# User_Interface.net
KiCad netlist of a schematic drawn in Altium Designer
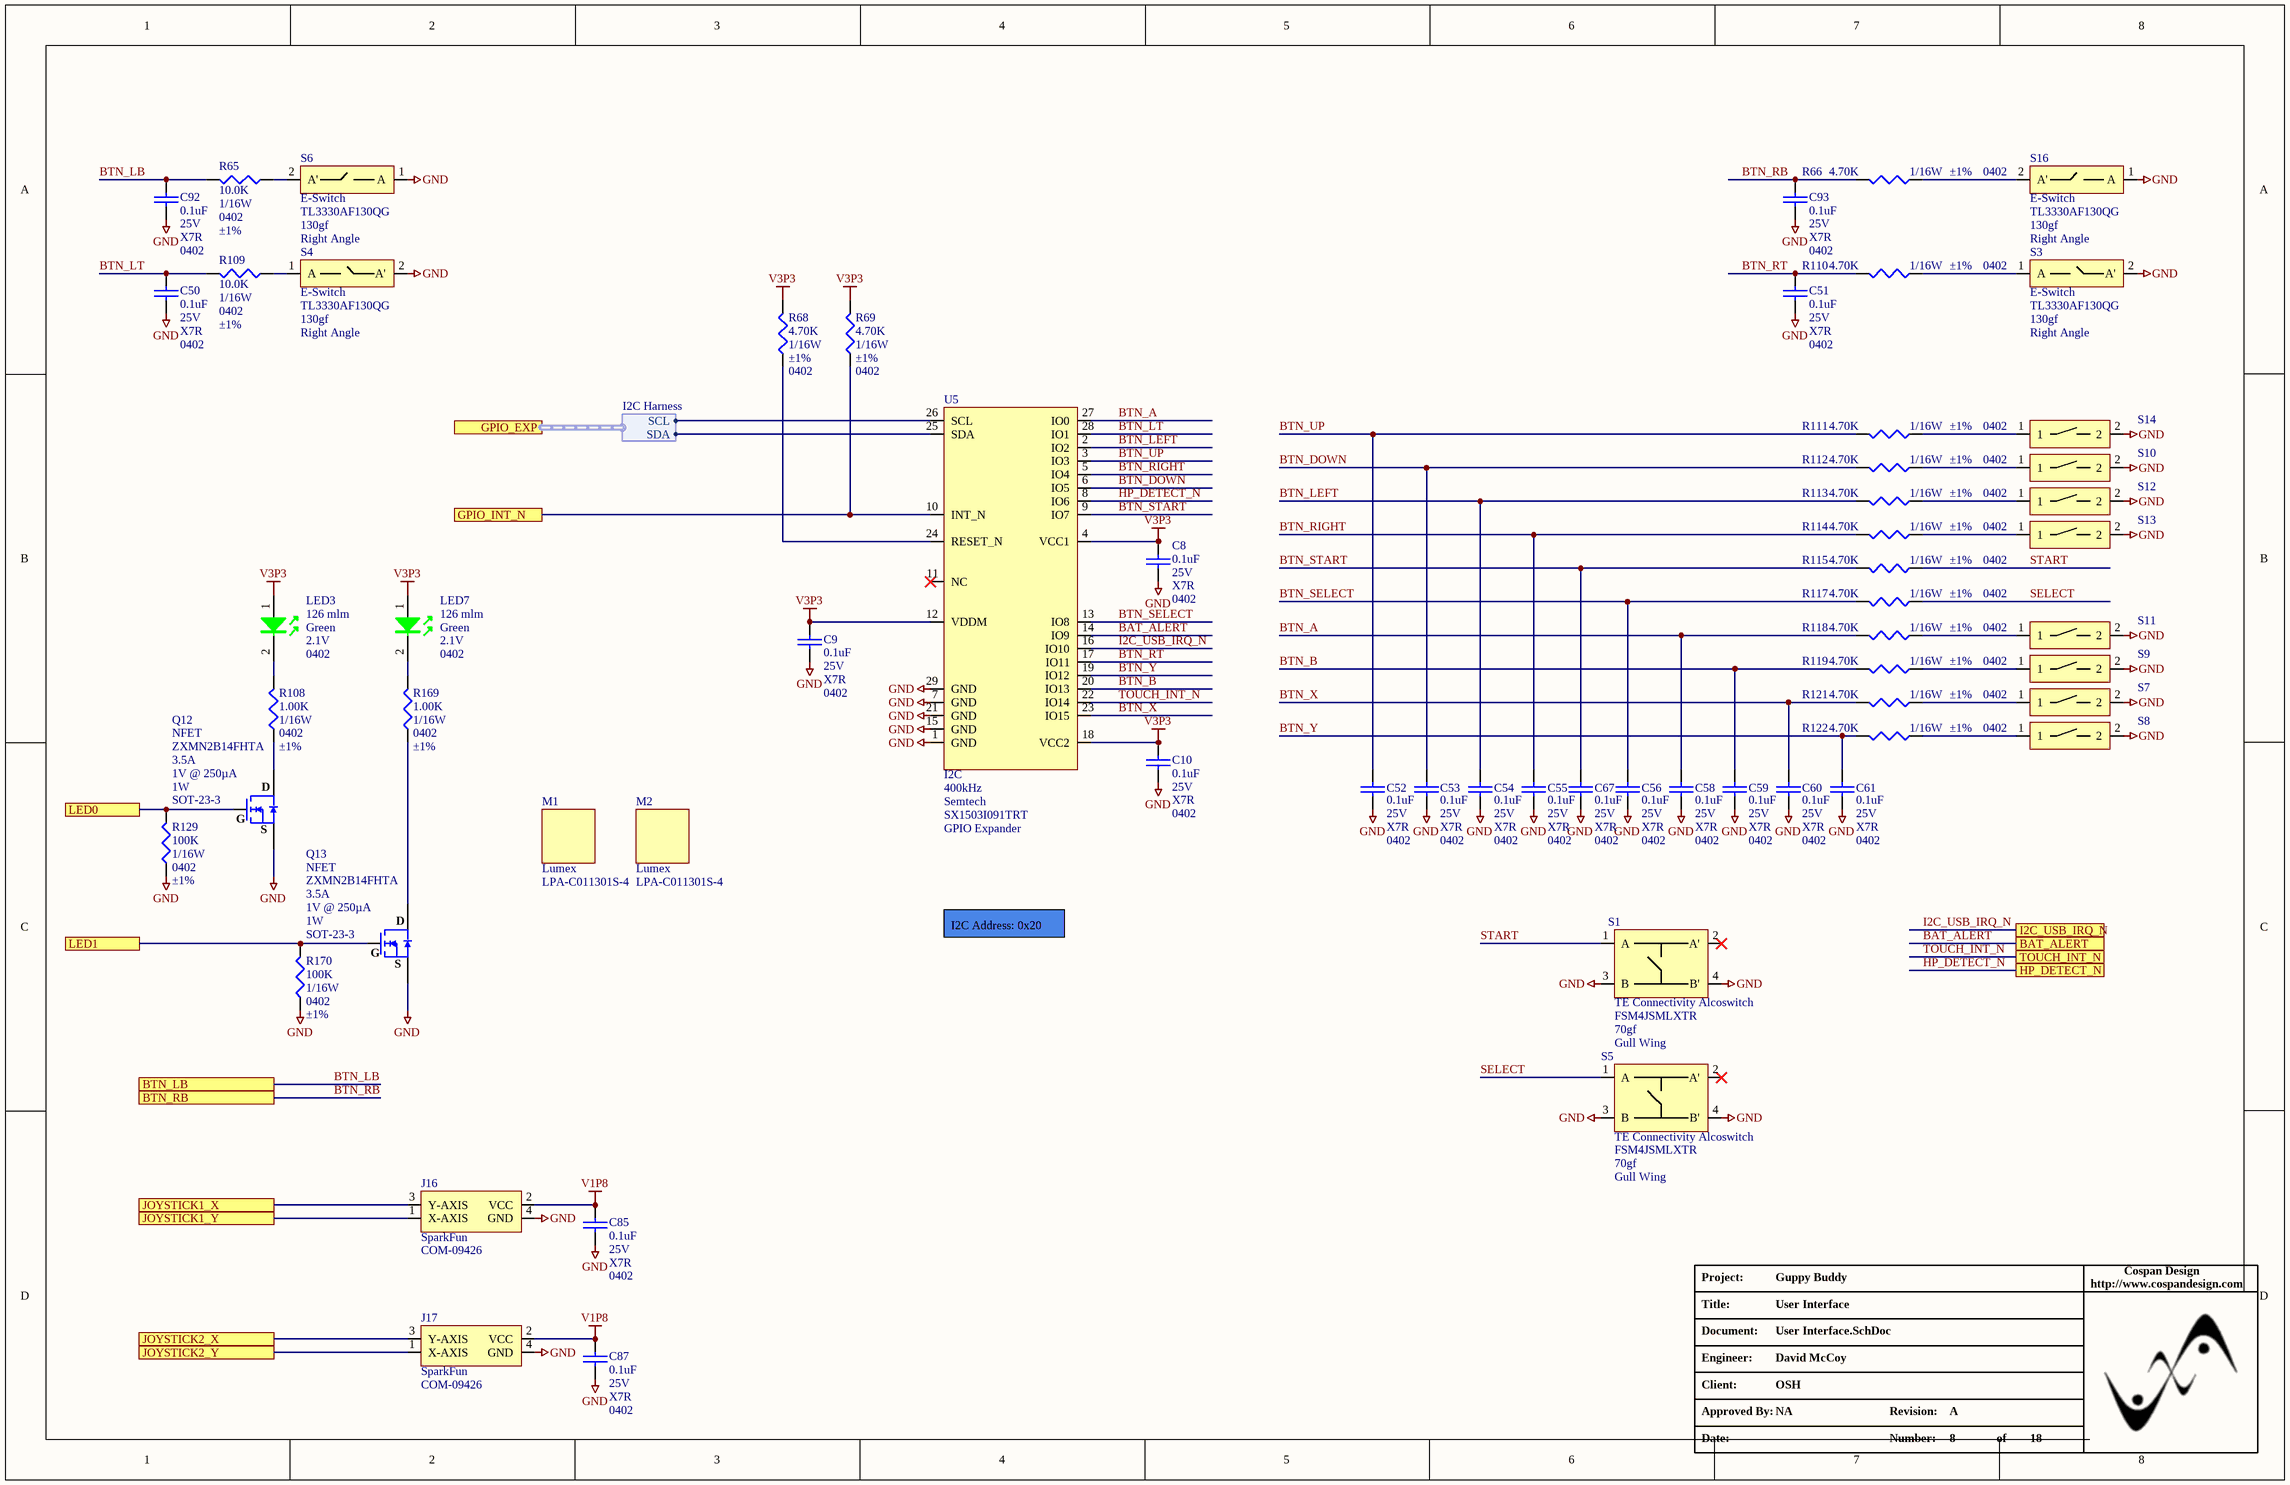
[diagram p0: User Interface.SchDoc]

(export (version "E")
  (design (tool "Eeschema 10.0.6"))
  (components
    (comp (ref "C8")
      (value "C_0402_0.1UF_25V")
      (footprint "C_0402")
      (description "CAP CER 0.1UF 25V X6S 0402")
      (fields
        (field (name "TOLERANCE") "10%")
        (field (name "CAPACITANCE") "0.1uF")
        (field (name "VOLTAGE - RATED") "25V")
        (field (name "TEMPERATURE COEFFICIENT") "X7R")
        (field (name "PACKAGE / CASE") "0402")
      )
      (libsource (lib "Cospan Design") (part "C_0402_0.1UF_25V"))
    )
    (comp (ref "C9")
      (value "C_0402_0.1UF_25V")
      (footprint "C_0402")
      (description "CAP CER 0.1UF 25V X6S 0402")
      (fields
        (field (name "TOLERANCE") "10%")
        (field (name "CAPACITANCE") "0.1uF")
        (field (name "VOLTAGE - RATED") "25V")
        (field (name "TEMPERATURE COEFFICIENT") "X7R")
        (field (name "PACKAGE / CASE") "0402")
      )
      (libsource (lib "Cospan Design") (part "C_0402_0.1UF_25V"))
    )
    (comp (ref "C10")
      (value "C_0402_0.1UF_25V")
      (footprint "C_0402")
      (description "CAP CER 0.1UF 25V X6S 0402")
      (fields
        (field (name "TOLERANCE") "10%")
        (field (name "CAPACITANCE") "0.1uF")
        (field (name "VOLTAGE - RATED") "25V")
        (field (name "TEMPERATURE COEFFICIENT") "X7R")
        (field (name "PACKAGE / CASE") "0402")
      )
      (libsource (lib "Cospan Design") (part "C_0402_0.1UF_25V"))
    )
    (comp (ref "C50")
      (value "C_0402_0.1UF_25V")
      (footprint "C_0402")
      (description "CAP CER 0.1UF 25V X6S 0402")
      (fields
        (field (name "TOLERANCE") "10%")
        (field (name "CAPACITANCE") "0.1uF")
        (field (name "VOLTAGE - RATED") "25V")
        (field (name "TEMPERATURE COEFFICIENT") "X7R")
        (field (name "PACKAGE / CASE") "0402")
      )
      (libsource (lib "Cospan Design") (part "C_0402_0.1UF_25V"))
    )
    (comp (ref "C51")
      (value "C_0402_0.1UF_25V")
      (footprint "C_0402")
      (description "CAP CER 0.1UF 25V X6S 0402")
      (fields
        (field (name "TOLERANCE") "10%")
        (field (name "CAPACITANCE") "0.1uF")
        (field (name "VOLTAGE - RATED") "25V")
        (field (name "TEMPERATURE COEFFICIENT") "X7R")
        (field (name "PACKAGE / CASE") "0402")
      )
      (libsource (lib "Cospan Design") (part "C_0402_0.1UF_25V"))
    )
    (comp (ref "C52")
      (value "C_0402_0.1UF_25V")
      (footprint "C_0402")
      (description "CAP CER 0.1UF 25V X6S 0402")
      (fields
        (field (name "TOLERANCE") "10%")
        (field (name "CAPACITANCE") "0.1uF")
        (field (name "VOLTAGE - RATED") "25V")
        (field (name "TEMPERATURE COEFFICIENT") "X7R")
        (field (name "PACKAGE / CASE") "0402")
      )
      (libsource (lib "Cospan Design") (part "C_0402_0.1UF_25V"))
    )
    (comp (ref "C53")
      (value "C_0402_0.1UF_25V")
      (footprint "C_0402")
      (description "CAP CER 0.1UF 25V X6S 0402")
      (fields
        (field (name "TOLERANCE") "10%")
        (field (name "CAPACITANCE") "0.1uF")
        (field (name "VOLTAGE - RATED") "25V")
        (field (name "TEMPERATURE COEFFICIENT") "X7R")
        (field (name "PACKAGE / CASE") "0402")
      )
      (libsource (lib "Cospan Design") (part "C_0402_0.1UF_25V"))
    )
    (comp (ref "C54")
      (value "C_0402_0.1UF_25V")
      (footprint "C_0402")
      (description "CAP CER 0.1UF 25V X6S 0402")
      (fields
        (field (name "TOLERANCE") "10%")
        (field (name "CAPACITANCE") "0.1uF")
        (field (name "VOLTAGE - RATED") "25V")
        (field (name "TEMPERATURE COEFFICIENT") "X7R")
        (field (name "PACKAGE / CASE") "0402")
      )
      (libsource (lib "Cospan Design") (part "C_0402_0.1UF_25V"))
    )
    (comp (ref "C55")
      (value "C_0402_0.1UF_25V")
      (footprint "C_0402")
      (description "CAP CER 0.1UF 25V X6S 0402")
      (fields
        (field (name "TOLERANCE") "10%")
        (field (name "CAPACITANCE") "0.1uF")
        (field (name "VOLTAGE - RATED") "25V")
        (field (name "TEMPERATURE COEFFICIENT") "X7R")
        (field (name "PACKAGE / CASE") "0402")
      )
      (libsource (lib "Cospan Design") (part "C_0402_0.1UF_25V"))
    )
    (comp (ref "C56")
      (value "C_0402_0.1UF_25V")
      (footprint "C_0402")
      (description "CAP CER 0.1UF 25V X6S 0402")
      (fields
        (field (name "TOLERANCE") "10%")
        (field (name "CAPACITANCE") "0.1uF")
        (field (name "VOLTAGE - RATED") "25V")
        (field (name "TEMPERATURE COEFFICIENT") "X7R")
        (field (name "PACKAGE / CASE") "0402")
      )
      (libsource (lib "Cospan Design") (part "C_0402_0.1UF_25V"))
    )
    (comp (ref "C58")
      (value "C_0402_0.1UF_25V")
      (footprint "C_0402")
      (description "CAP CER 0.1UF 25V X6S 0402")
      (fields
        (field (name "TOLERANCE") "10%")
        (field (name "CAPACITANCE") "0.1uF")
        (field (name "VOLTAGE - RATED") "25V")
        (field (name "TEMPERATURE COEFFICIENT") "X7R")
        (field (name "PACKAGE / CASE") "0402")
      )
      (libsource (lib "Cospan Design") (part "C_0402_0.1UF_25V"))
    )
    (comp (ref "C59")
      (value "C_0402_0.1UF_25V")
      (footprint "C_0402")
      (description "CAP CER 0.1UF 25V X6S 0402")
      (fields
        (field (name "TOLERANCE") "10%")
        (field (name "CAPACITANCE") "0.1uF")
        (field (name "VOLTAGE - RATED") "25V")
        (field (name "TEMPERATURE COEFFICIENT") "X7R")
        (field (name "PACKAGE / CASE") "0402")
      )
      (libsource (lib "Cospan Design") (part "C_0402_0.1UF_25V"))
    )
    (comp (ref "C60")
      (value "C_0402_0.1UF_25V")
      (footprint "C_0402")
      (description "CAP CER 0.1UF 25V X6S 0402")
      (fields
        (field (name "TOLERANCE") "10%")
        (field (name "CAPACITANCE") "0.1uF")
        (field (name "VOLTAGE - RATED") "25V")
        (field (name "TEMPERATURE COEFFICIENT") "X7R")
        (field (name "PACKAGE / CASE") "0402")
      )
      (libsource (lib "Cospan Design") (part "C_0402_0.1UF_25V"))
    )
    (comp (ref "C61")
      (value "C_0402_0.1UF_25V")
      (footprint "C_0402")
      (description "CAP CER 0.1UF 25V X6S 0402")
      (fields
        (field (name "TOLERANCE") "10%")
        (field (name "CAPACITANCE") "0.1uF")
        (field (name "VOLTAGE - RATED") "25V")
        (field (name "TEMPERATURE COEFFICIENT") "X7R")
        (field (name "PACKAGE / CASE") "0402")
      )
      (libsource (lib "Cospan Design") (part "C_0402_0.1UF_25V"))
    )
    (comp (ref "C67")
      (value "C_0402_0.1UF_25V")
      (footprint "C_0402")
      (description "CAP CER 0.1UF 25V X6S 0402")
      (fields
        (field (name "TOLERANCE") "10%")
        (field (name "CAPACITANCE") "0.1uF")
        (field (name "VOLTAGE - RATED") "25V")
        (field (name "TEMPERATURE COEFFICIENT") "X7R")
        (field (name "PACKAGE / CASE") "0402")
      )
      (libsource (lib "Cospan Design") (part "C_0402_0.1UF_25V"))
    )
    (comp (ref "C85")
      (value "C_0402_0.1UF_25V")
      (footprint "C_0402")
      (description "CAP CER 0.1UF 25V X6S 0402")
      (fields
        (field (name "TOLERANCE") "10%")
        (field (name "CAPACITANCE") "0.1uF")
        (field (name "VOLTAGE - RATED") "25V")
        (field (name "TEMPERATURE COEFFICIENT") "X7R")
        (field (name "PACKAGE / CASE") "0402")
      )
      (libsource (lib "Cospan Design") (part "C_0402_0.1UF_25V"))
    )
    (comp (ref "C87")
      (value "C_0402_0.1UF_25V")
      (footprint "C_0402")
      (description "CAP CER 0.1UF 25V X6S 0402")
      (fields
        (field (name "TOLERANCE") "10%")
        (field (name "CAPACITANCE") "0.1uF")
        (field (name "VOLTAGE - RATED") "25V")
        (field (name "TEMPERATURE COEFFICIENT") "X7R")
        (field (name "PACKAGE / CASE") "0402")
      )
      (libsource (lib "Cospan Design") (part "C_0402_0.1UF_25V"))
    )
    (comp (ref "C92")
      (value "C_0402_0.1UF_25V")
      (footprint "C_0402")
      (description "CAP CER 0.1UF 25V X6S 0402")
      (fields
        (field (name "TOLERANCE") "10%")
        (field (name "CAPACITANCE") "0.1uF")
        (field (name "VOLTAGE - RATED") "25V")
        (field (name "TEMPERATURE COEFFICIENT") "X7R")
        (field (name "PACKAGE / CASE") "0402")
      )
      (libsource (lib "Cospan Design") (part "C_0402_0.1UF_25V"))
    )
    (comp (ref "C93")
      (value "C_0402_0.1UF_25V")
      (footprint "C_0402")
      (description "CAP CER 0.1UF 25V X6S 0402")
      (fields
        (field (name "TOLERANCE") "10%")
        (field (name "CAPACITANCE") "0.1uF")
        (field (name "VOLTAGE - RATED") "25V")
        (field (name "TEMPERATURE COEFFICIENT") "X7R")
        (field (name "PACKAGE / CASE") "0402")
      )
      (libsource (lib "Cospan Design") (part "C_0402_0.1UF_25V"))
    )
    (comp (ref "J16")
      (value "J_PSP1000")
      (footprint "JOYSTICK_PSP1000")
      (description "THUMB SLIDE JOYSTICK")
      (fields
        (field (name "MANUFACTURER 1") "SparkFun")
        (field (name "MANUFACTURER PART NUMBER 1") "COM-09426")
      )
      (libsource (lib "Cospan Design") (part "J_PSP1000"))
    )
    (comp (ref "J17")
      (value "J_PSP1000")
      (footprint "JOYSTICK_PSP1000")
      (description "THUMB SLIDE JOYSTICK")
      (fields
        (field (name "MANUFACTURER 1") "SparkFun")
        (field (name "MANUFACTURER PART NUMBER 1") "COM-09426")
      )
      (libsource (lib "Cospan Design") (part "J_PSP1000"))
    )
    (comp (ref "LED3")
      (value "LED_GRN_0402")
      (footprint "DIOM1005X07L_GREEN")
      (description "LED 1X0.5MM 570NM GN WTR CLR SMD")
      (fields
        (field (name "MANUFACTURER") "Kingbright Corp")
        (field (name "MANUFACTURER PART NUMBER") "APHHS1005CGCK")
        (field (name "LUMINOUS FLUX @ CURRENT - TEST") "126 mlm")
        (field (name "COLOR") "Green")
        (field (name "VOLTAGE - FORWARD (VF) TYP") "2.1V")
        (field (name "PACKAGE / CASE") "0402")
      )
      (libsource (lib "Main Library") (part "LED_GRN_0402"))
    )
    (comp (ref "LED7")
      (value "LED_GRN_0402")
      (footprint "DIOM1005X07L_GREEN")
      (description "LED 1X0.5MM 570NM GN WTR CLR SMD")
      (fields
        (field (name "MANUFACTURER") "Kingbright Corp")
        (field (name "MANUFACTURER PART NUMBER") "APHHS1005CGCK")
        (field (name "LUMINOUS FLUX @ CURRENT - TEST") "126 mlm")
        (field (name "COLOR") "Green")
        (field (name "VOLTAGE - FORWARD (VF) TYP") "2.1V")
        (field (name "PACKAGE / CASE") "0402")
      )
      (libsource (lib "Main Library") (part "LED_GRN_0402"))
    )
    (comp (ref "M1")
      (value "M_LIGHT_PIPE")
      (footprint "SINGLE_LIGHT_PIPE")
      (description "LIGHT PIPE 4MM SINGLE VERT SMD")
      (fields
        (field (name "MANUFACTURER 1") "Lumex")
        (field (name "MANUFACTURER PART NUMBER 1") "LPA-C011301S-4")
      )
      (libsource (lib "Cospan Design") (part "M_LIGHT_PIPE"))
    )
    (comp (ref "M2")
      (value "M_LIGHT_PIPE")
      (footprint "SINGLE_LIGHT_PIPE")
      (description "LIGHT PIPE 4MM SINGLE VERT SMD")
      (fields
        (field (name "MANUFACTURER 1") "Lumex")
        (field (name "MANUFACTURER PART NUMBER 1") "LPA-C011301S-4")
      )
      (libsource (lib "Cospan Design") (part "M_LIGHT_PIPE"))
    )
    (comp (ref "Q12")
      (value "NFET")
      (footprint "SOT-23A")
      (description "MOSFET N-CH 20V 3.5A SOT23-3")
      (fields
        (field (name "MANUFACTURER") "Diodes Incorporated")
        (field (name "MANUFACTURER PART NUMBER") "ZXMN2B14FHTA")
        (field (name "CURRENT - CONTINUOUS DRAIN (ID) @ 25° C") "3.5A")
        (field (name "VGS(TH) (MAX) @ ID") "1V @ 250µA")
        (field (name "POWER - MAX") "1W")
        (field (name "PACKAGE / CASE") "SOT-23-3")
      )
      (libsource (lib "Main LibraryX") (part "Q_NFET_3.50A_SOT23"))
    )
    (comp (ref "Q13")
      (value "NFET")
      (footprint "SOT-23A")
      (description "MOSFET N-CH 20V 3.5A SOT23-3")
      (fields
        (field (name "MANUFACTURER") "Diodes Incorporated")
        (field (name "MANUFACTURER PART NUMBER") "ZXMN2B14FHTA")
        (field (name "CURRENT - CONTINUOUS DRAIN (ID) @ 25° C") "3.5A")
        (field (name "VGS(TH) (MAX) @ ID") "1V @ 250µA")
        (field (name "POWER - MAX") "1W")
        (field (name "PACKAGE / CASE") "SOT-23-3")
      )
      (libsource (lib "Main LibraryX") (part "Q_NFET_3.50A_SOT23"))
    )
    (comp (ref "R65")
      (value "R_0402_10.0K")
      (footprint "R_0402")
      (description "RES 10.0K OHM 1/16W 1% 0402 SMD")
      (fields
        (field (name "MANUFACTURER") "Stackpole Electronics Inc")
        (field (name "MANUFACTURER PART NUMBER") "RMCF0402FT10K0")
        (field (name "RESISTANCE IN OHMS") "10.0K")
        (field (name "POWER (WATTS)") "1/16W")
        (field (name "CASE") "0402")
        (field (name "TOLERANCE") "±1%")
      )
      (libsource (lib "Cospan Design") (part "R_0402_10.0K"))
    )
    (comp (ref "R66")
      (value "4.7k Ohms")
      (footprint "R_0402")
      (description "RES 4.70K OHM 1/16W 1% 0402 SMD")
      (fields
        (field (name "MANUFACTURER") "Yageo")
        (field (name "MANUFACTURER PART NUMBER") "RC0402FR-074K7L")
        (field (name "RESISTANCE IN OHMS") "4.70K")
        (field (name "POWER (WATTS)") "1/16W")
        (field (name "TOLERANCE") "±1%")
        (field (name "CASE") "0402")
      )
      (libsource (lib "Main Library") (part "R_0402_4.70K"))
    )
    (comp (ref "R68")
      (value "4.7k Ohms")
      (footprint "R_0402")
      (description "RES 4.70K OHM 1/16W 1% 0402 SMD")
      (fields
        (field (name "MANUFACTURER") "Yageo")
        (field (name "MANUFACTURER PART NUMBER") "RC0402FR-074K7L")
        (field (name "RESISTANCE IN OHMS") "4.70K")
        (field (name "POWER (WATTS)") "1/16W")
        (field (name "TOLERANCE") "±1%")
        (field (name "CASE") "0402")
      )
      (libsource (lib "Main Library") (part "R_0402_4.70K"))
    )
    (comp (ref "R69")
      (value "4.7k Ohms")
      (footprint "R_0402")
      (description "RES 4.70K OHM 1/16W 1% 0402 SMD")
      (fields
        (field (name "MANUFACTURER") "Yageo")
        (field (name "MANUFACTURER PART NUMBER") "RC0402FR-074K7L")
        (field (name "RESISTANCE IN OHMS") "4.70K")
        (field (name "POWER (WATTS)") "1/16W")
        (field (name "TOLERANCE") "±1%")
        (field (name "CASE") "0402")
      )
      (libsource (lib "Main Library") (part "R_0402_4.70K"))
    )
    (comp (ref "R108")
      (value "1.0k Ohms")
      (footprint "R_0402")
      (description "RES 1.00K OHM 1/16W 1% 0402 SMD")
      (fields
        (field (name "MANUFACTURER") "Yageo")
        (field (name "MANUFACTURER PART NUMBER") "RC0402FR-071KL")
        (field (name "RESISTANCE IN OHMS") "1.00K")
        (field (name "POWER (WATTS)") "1/16W")
        (field (name "CASE") "0402")
        (field (name "TOLERANCE") "±1%")
      )
      (libsource (lib "Main Library") (part "R_0402_1.0K"))
    )
    (comp (ref "R109")
      (value "R_0402_10.0K")
      (footprint "R_0402")
      (description "RES 10.0K OHM 1/16W 1% 0402 SMD")
      (fields
        (field (name "MANUFACTURER") "Stackpole Electronics Inc")
        (field (name "MANUFACTURER PART NUMBER") "RMCF0402FT10K0")
        (field (name "RESISTANCE IN OHMS") "10.0K")
        (field (name "POWER (WATTS)") "1/16W")
        (field (name "CASE") "0402")
        (field (name "TOLERANCE") "±1%")
      )
      (libsource (lib "Cospan Design") (part "R_0402_10.0K"))
    )
    (comp (ref "R110")
      (value "4.7k Ohms")
      (footprint "R_0402")
      (description "RES 4.70K OHM 1/16W 1% 0402 SMD")
      (fields
        (field (name "MANUFACTURER") "Yageo")
        (field (name "MANUFACTURER PART NUMBER") "RC0402FR-074K7L")
        (field (name "RESISTANCE IN OHMS") "4.70K")
        (field (name "POWER (WATTS)") "1/16W")
        (field (name "TOLERANCE") "±1%")
        (field (name "CASE") "0402")
      )
      (libsource (lib "Main Library") (part "R_0402_4.70K"))
    )
    (comp (ref "R111")
      (value "4.7k Ohms")
      (footprint "R_0402")
      (description "RES 4.70K OHM 1/16W 1% 0402 SMD")
      (fields
        (field (name "MANUFACTURER") "Yageo")
        (field (name "MANUFACTURER PART NUMBER") "RC0402FR-074K7L")
        (field (name "RESISTANCE IN OHMS") "4.70K")
        (field (name "POWER (WATTS)") "1/16W")
        (field (name "TOLERANCE") "±1%")
        (field (name "CASE") "0402")
      )
      (libsource (lib "Main Library") (part "R_0402_4.70K"))
    )
    (comp (ref "R112")
      (value "4.7k Ohms")
      (footprint "R_0402")
      (description "RES 4.70K OHM 1/16W 1% 0402 SMD")
      (fields
        (field (name "MANUFACTURER") "Yageo")
        (field (name "MANUFACTURER PART NUMBER") "RC0402FR-074K7L")
        (field (name "RESISTANCE IN OHMS") "4.70K")
        (field (name "POWER (WATTS)") "1/16W")
        (field (name "TOLERANCE") "±1%")
        (field (name "CASE") "0402")
      )
      (libsource (lib "Main Library") (part "R_0402_4.70K"))
    )
    (comp (ref "R113")
      (value "4.7k Ohms")
      (footprint "R_0402")
      (description "RES 4.70K OHM 1/16W 1% 0402 SMD")
      (fields
        (field (name "MANUFACTURER") "Yageo")
        (field (name "MANUFACTURER PART NUMBER") "RC0402FR-074K7L")
        (field (name "RESISTANCE IN OHMS") "4.70K")
        (field (name "POWER (WATTS)") "1/16W")
        (field (name "TOLERANCE") "±1%")
        (field (name "CASE") "0402")
      )
      (libsource (lib "Main Library") (part "R_0402_4.70K"))
    )
    (comp (ref "R114")
      (value "4.7k Ohms")
      (footprint "R_0402")
      (description "RES 4.70K OHM 1/16W 1% 0402 SMD")
      (fields
        (field (name "MANUFACTURER") "Yageo")
        (field (name "MANUFACTURER PART NUMBER") "RC0402FR-074K7L")
        (field (name "RESISTANCE IN OHMS") "4.70K")
        (field (name "POWER (WATTS)") "1/16W")
        (field (name "TOLERANCE") "±1%")
        (field (name "CASE") "0402")
      )
      (libsource (lib "Main Library") (part "R_0402_4.70K"))
    )
    (comp (ref "R115")
      (value "4.7k Ohms")
      (footprint "R_0402")
      (description "RES 4.70K OHM 1/16W 1% 0402 SMD")
      (fields
        (field (name "MANUFACTURER") "Yageo")
        (field (name "MANUFACTURER PART NUMBER") "RC0402FR-074K7L")
        (field (name "RESISTANCE IN OHMS") "4.70K")
        (field (name "POWER (WATTS)") "1/16W")
        (field (name "TOLERANCE") "±1%")
        (field (name "CASE") "0402")
      )
      (libsource (lib "Main Library") (part "R_0402_4.70K"))
    )
    (comp (ref "R117")
      (value "4.7k Ohms")
      (footprint "R_0402")
      (description "RES 4.70K OHM 1/16W 1% 0402 SMD")
      (fields
        (field (name "MANUFACTURER") "Yageo")
        (field (name "MANUFACTURER PART NUMBER") "RC0402FR-074K7L")
        (field (name "RESISTANCE IN OHMS") "4.70K")
        (field (name "POWER (WATTS)") "1/16W")
        (field (name "TOLERANCE") "±1%")
        (field (name "CASE") "0402")
      )
      (libsource (lib "Main Library") (part "R_0402_4.70K"))
    )
    (comp (ref "R118")
      (value "4.7k Ohms")
      (footprint "R_0402")
      (description "RES 4.70K OHM 1/16W 1% 0402 SMD")
      (fields
        (field (name "MANUFACTURER") "Yageo")
        (field (name "MANUFACTURER PART NUMBER") "RC0402FR-074K7L")
        (field (name "RESISTANCE IN OHMS") "4.70K")
        (field (name "POWER (WATTS)") "1/16W")
        (field (name "TOLERANCE") "±1%")
        (field (name "CASE") "0402")
      )
      (libsource (lib "Main Library") (part "R_0402_4.70K"))
    )
    (comp (ref "R119")
      (value "4.7k Ohms")
      (footprint "R_0402")
      (description "RES 4.70K OHM 1/16W 1% 0402 SMD")
      (fields
        (field (name "MANUFACTURER") "Yageo")
        (field (name "MANUFACTURER PART NUMBER") "RC0402FR-074K7L")
        (field (name "RESISTANCE IN OHMS") "4.70K")
        (field (name "POWER (WATTS)") "1/16W")
        (field (name "TOLERANCE") "±1%")
        (field (name "CASE") "0402")
      )
      (libsource (lib "Main Library") (part "R_0402_4.70K"))
    )
    (comp (ref "R121")
      (value "4.7k Ohms")
      (footprint "R_0402")
      (description "RES 4.70K OHM 1/16W 1% 0402 SMD")
      (fields
        (field (name "MANUFACTURER") "Yageo")
        (field (name "MANUFACTURER PART NUMBER") "RC0402FR-074K7L")
        (field (name "RESISTANCE IN OHMS") "4.70K")
        (field (name "POWER (WATTS)") "1/16W")
        (field (name "TOLERANCE") "±1%")
        (field (name "CASE") "0402")
      )
      (libsource (lib "Main Library") (part "R_0402_4.70K"))
    )
    (comp (ref "R122")
      (value "4.7k Ohms")
      (footprint "R_0402")
      (description "RES 4.70K OHM 1/16W 1% 0402 SMD")
      (fields
        (field (name "MANUFACTURER") "Yageo")
        (field (name "MANUFACTURER PART NUMBER") "RC0402FR-074K7L")
        (field (name "RESISTANCE IN OHMS") "4.70K")
        (field (name "POWER (WATTS)") "1/16W")
        (field (name "TOLERANCE") "±1%")
        (field (name "CASE") "0402")
      )
      (libsource (lib "Main Library") (part "R_0402_4.70K"))
    )
    (comp (ref "R129")
      (value "R_0402_100.0K")
      (footprint "R_0402")
      (description "RES 100K OHM 1/16W 1% 0402 SMD")
      (fields
        (field (name "MANUFACTURER") "Stackpole Electronics Inc")
        (field (name "MANUFACTURER PART NUMBER") "RMCF0402FT100K")
        (field (name "RESISTANCE IN OHMS") "100K")
        (field (name "POWER (WATTS)") "1/16W")
        (field (name "CASE") "0402")
        (field (name "TOLERANCE") "±1%")
      )
      (libsource (lib "Main Library") (part "R_0402_100.0K"))
    )
    (comp (ref "R169")
      (value "1.0k Ohms")
      (footprint "R_0402")
      (description "RES 1.00K OHM 1/16W 1% 0402 SMD")
      (fields
        (field (name "MANUFACTURER") "Yageo")
        (field (name "MANUFACTURER PART NUMBER") "RC0402FR-071KL")
        (field (name "RESISTANCE IN OHMS") "1.00K")
        (field (name "POWER (WATTS)") "1/16W")
        (field (name "CASE") "0402")
        (field (name "TOLERANCE") "±1%")
      )
      (libsource (lib "Main Library") (part "R_0402_1.0K"))
    )
    (comp (ref "R170")
      (value "R_0402_100.0K")
      (footprint "R_0402")
      (description "RES 100K OHM 1/16W 1% 0402 SMD")
      (fields
        (field (name "MANUFACTURER") "Stackpole Electronics Inc")
        (field (name "MANUFACTURER PART NUMBER") "RMCF0402FT100K")
        (field (name "RESISTANCE IN OHMS") "100K")
        (field (name "POWER (WATTS)") "1/16W")
        (field (name "CASE") "0402")
        (field (name "TOLERANCE") "±1%")
      )
      (libsource (lib "Main Library") (part "R_0402_100.0K"))
    )
    (comp (ref "S1")
      (value "S_TACTILE_1571563_2_BUTTON")
      (footprint "TACTILE_1571563_2")
      (description "SWITCH TACTILE SPST-NO 0.05A 24V")
      (fields
        (field (name "MANUFACTURER") "TE Connectivity Alcoswitch")
        (field (name "MANUFACTURER PART NUMBER") "FSM4JSMLXTR")
        (field (name "OPERATING FORCE") "70gf")
        (field (name "TERMINATION") "Gull Wing")
      )
      (libsource (lib "Cospan Design") (part "S_TACTILE_1571563_2_BUTTON"))
    )
    (comp (ref "S3")
      (value "S_TACTILE_ RA_TL3330AF130QG_BUTTON")
      (footprint "TL3330AF130QG")
      (description "SWITCH TACTILE SPST-NO 0.05A 12V")
      (fields
        (field (name "MANUFACTURER") "E-Switch")
        (field (name "MANUFACTURER PART NUMBER") "TL3330AF130QG")
        (field (name "OPERATING FORCE") "130gf")
        (field (name "ORIENTATION") "Right Angle")
      )
      (libsource (lib "Cospan Design") (part "S_TACTILE_ RA_TL3330AF130QG_BUTTON"))
    )
    (comp (ref "S4")
      (value "S_TACTILE_ RA_TL3330AF130QG_BUTTON")
      (footprint "TL3330AF130QG")
      (description "SWITCH TACTILE SPST-NO 0.05A 12V")
      (fields
        (field (name "MANUFACTURER") "E-Switch")
        (field (name "MANUFACTURER PART NUMBER") "TL3330AF130QG")
        (field (name "OPERATING FORCE") "130gf")
        (field (name "ORIENTATION") "Right Angle")
      )
      (libsource (lib "Cospan Design") (part "S_TACTILE_ RA_TL3330AF130QG_BUTTON"))
    )
    (comp (ref "S5")
      (value "S_TACTILE_1571563_2_BUTTON")
      (footprint "TACTILE_1571563_2")
      (description "SWITCH TACTILE SPST-NO 0.05A 24V")
      (fields
        (field (name "MANUFACTURER") "TE Connectivity Alcoswitch")
        (field (name "MANUFACTURER PART NUMBER") "FSM4JSMLXTR")
        (field (name "OPERATING FORCE") "70gf")
        (field (name "TERMINATION") "Gull Wing")
      )
      (libsource (lib "Cospan Design") (part "S_TACTILE_1571563_2_BUTTON"))
    )
    (comp (ref "S6")
      (value "S_TACTILE_ RA_TL3330AF130QG_BUTTON")
      (footprint "TL3330AF130QG")
      (description "SWITCH TACTILE SPST-NO 0.05A 12V")
      (fields
        (field (name "MANUFACTURER") "E-Switch")
        (field (name "MANUFACTURER PART NUMBER") "TL3330AF130QG")
        (field (name "OPERATING FORCE") "130gf")
        (field (name "ORIENTATION") "Right Angle")
      )
      (libsource (lib "") (part "S_TACTILE_ RA_TL3330AF130QG_BUTTON_1"))
    )
    (comp (ref "S7")
      (value "S_GB_BTN")
      (footprint "GB_BUTTON")
      (libsource (lib "Cospan Design") (part "S_GB_BTN"))
    )
    (comp (ref "S8")
      (value "S_GB_BTN")
      (footprint "GB_BUTTON")
      (libsource (lib "Cospan Design") (part "S_GB_BTN"))
    )
    (comp (ref "S9")
      (value "S_GB_BTN")
      (footprint "GB_BUTTON")
      (libsource (lib "Cospan Design") (part "S_GB_BTN"))
    )
    (comp (ref "S10")
      (value "S_GB_BTN")
      (footprint "GB_BUTTON")
      (libsource (lib "Cospan Design") (part "S_GB_BTN"))
    )
    (comp (ref "S11")
      (value "S_GB_BTN")
      (footprint "GB_BUTTON")
      (libsource (lib "Cospan Design") (part "S_GB_BTN"))
    )
    (comp (ref "S12")
      (value "S_GB_BTN")
      (footprint "GB_BUTTON")
      (libsource (lib "Cospan Design") (part "S_GB_BTN"))
    )
    (comp (ref "S13")
      (value "S_GB_BTN")
      (footprint "GB_BUTTON")
      (libsource (lib "Cospan Design") (part "S_GB_BTN"))
    )
    (comp (ref "S14")
      (value "S_GB_BTN")
      (footprint "GB_BUTTON")
      (libsource (lib "Cospan Design") (part "S_GB_BTN"))
    )
    (comp (ref "S16")
      (value "S_TACTILE_ RA_TL3330AF130QG_BUTTON")
      (footprint "TL3330AF130QG")
      (description "SWITCH TACTILE SPST-NO 0.05A 12V")
      (fields
        (field (name "MANUFACTURER") "E-Switch")
        (field (name "MANUFACTURER PART NUMBER") "TL3330AF130QG")
        (field (name "OPERATING FORCE") "130gf")
        (field (name "ORIENTATION") "Right Angle")
      )
      (libsource (lib "") (part "S_TACTILE_ RA_TL3330AF130QG_BUTTON_1"))
    )
    (comp (ref "U5")
      (value "U_SX1503I091TRT")
      (footprint "QFN40P400X400X60_HS-29N")
      (description "IC GPIO EXPANDER I2C 16CH 28-QFN")
      (fields
        (field (name "INTERFACE") "I2C")
        (field (name "FREQUENCY") "400kHz")
        (field (name "MANUFACTURER 1") "Semtech")
        (field (name "MANUFACTURER PART NUMBER 1") "SX1503I091TRT")
        (field (name "SHORT DESC") "GPIO Expander")
      )
      (libsource (lib "Cospan Design") (part "U_SX1503I091TRT"))
    )
  )
  (nets
    (net (code "3") (name "/BAT_ALERT") (class "Default")
      (node (ref "U5") (pin "14") (pinfunction "IO9_14") (pintype "passive"))
    )
    (net (code "4") (name "/BTN_A") (class "Default")
      (node (ref "C58") (pin "2") (pinfunction "2_2") (pintype "passive"))
      (node (ref "R118") (pin "1") (pinfunction "1_1") (pintype "passive"))
      (node (ref "U5") (pin "27") (pinfunction "IO0_27") (pintype "passive"))
    )
    (net (code "5") (name "/BTN_B") (class "Default")
      (node (ref "C59") (pin "2") (pinfunction "2_2") (pintype "passive"))
      (node (ref "R119") (pin "1") (pinfunction "1_1") (pintype "passive"))
      (node (ref "U5") (pin "20") (pinfunction "IO13_20") (pintype "passive"))
    )
    (net (code "6") (name "/BTN_DOWN") (class "Default")
      (node (ref "C53") (pin "2") (pinfunction "2_2") (pintype "passive"))
      (node (ref "R112") (pin "1") (pinfunction "1_1") (pintype "passive"))
      (node (ref "U5") (pin "6") (pinfunction "IO5_6") (pintype "passive"))
    )
    (net (code "7") (name "/BTN_LB") (class "Default")
      (node (ref "C92") (pin "2") (pinfunction "2_2") (pintype "passive"))
      (node (ref "R65") (pin "1") (pinfunction "1_1") (pintype "passive"))
    )
    (net (code "8") (name "/BTN_LEFT") (class "Default")
      (node (ref "C54") (pin "2") (pinfunction "2_2") (pintype "passive"))
      (node (ref "R113") (pin "1") (pinfunction "1_1") (pintype "passive"))
      (node (ref "U5") (pin "2") (pinfunction "IO2_2") (pintype "passive"))
    )
    (net (code "9") (name "/BTN_LT") (class "Default")
      (node (ref "C50") (pin "2") (pinfunction "2_2") (pintype "passive"))
      (node (ref "R109") (pin "1") (pinfunction "1_1") (pintype "passive"))
      (node (ref "U5") (pin "28") (pinfunction "IO1_28") (pintype "passive"))
    )
    (net (code "10") (name "/BTN_RB") (class "Default")
      (node (ref "C93") (pin "2") (pinfunction "2_2") (pintype "passive"))
      (node (ref "R66") (pin "1") (pinfunction "1_1") (pintype "passive"))
    )
    (net (code "11") (name "/BTN_RIGHT") (class "Default")
      (node (ref "C55") (pin "2") (pinfunction "2_2") (pintype "passive"))
      (node (ref "R114") (pin "1") (pinfunction "1_1") (pintype "passive"))
      (node (ref "U5") (pin "5") (pinfunction "IO4_5") (pintype "passive"))
    )
    (net (code "12") (name "/BTN_RT") (class "Default")
      (node (ref "C51") (pin "2") (pinfunction "2_2") (pintype "passive"))
      (node (ref "R110") (pin "1") (pinfunction "1_1") (pintype "passive"))
      (node (ref "U5") (pin "17") (pinfunction "IO11_17") (pintype "passive"))
    )
    (net (code "13") (name "/BTN_SELECT") (class "Default")
      (node (ref "C56") (pin "2") (pinfunction "2_2") (pintype "passive"))
      (node (ref "R117") (pin "1") (pinfunction "1_1") (pintype "passive"))
      (node (ref "U5") (pin "13") (pinfunction "IO8_13") (pintype "passive"))
    )
    (net (code "14") (name "/BTN_START") (class "Default")
      (node (ref "C67") (pin "2") (pinfunction "2_2") (pintype "passive"))
      (node (ref "R115") (pin "1") (pinfunction "1_1") (pintype "passive"))
      (node (ref "U5") (pin "9") (pinfunction "IO7_9") (pintype "passive"))
    )
    (net (code "15") (name "/BTN_UP") (class "Default")
      (node (ref "C52") (pin "2") (pinfunction "2_2") (pintype "passive"))
      (node (ref "R111") (pin "1") (pinfunction "1_1") (pintype "passive"))
      (node (ref "U5") (pin "3") (pinfunction "IO3_3") (pintype "passive"))
    )
    (net (code "16") (name "/BTN_X") (class "Default")
      (node (ref "C60") (pin "2") (pinfunction "2_2") (pintype "passive"))
      (node (ref "R121") (pin "1") (pinfunction "1_1") (pintype "passive"))
      (node (ref "U5") (pin "23") (pinfunction "IO15_23") (pintype "passive"))
    )
    (net (code "17") (name "/BTN_Y") (class "Default")
      (node (ref "C61") (pin "2") (pinfunction "2_2") (pintype "passive"))
      (node (ref "R122") (pin "1") (pinfunction "1_1") (pintype "passive"))
      (node (ref "U5") (pin "19") (pinfunction "IO12_19") (pintype "passive"))
    )
    (net (code "18") (name "/GPIO_INT_N") (class "Default")
      (node (ref "R69") (pin "2") (pinfunction "2_2") (pintype "passive"))
      (node (ref "U5") (pin "10") (pinfunction "INT_N_10") (pintype "passive"))
    )
    (net (code "19") (name "/HP_DETECT_N") (class "Default")
      (node (ref "U5") (pin "8") (pinfunction "IO6_8") (pintype "passive"))
    )
    (net (code "20") (name "/I2C_USB_IRQ_N") (class "Default")
      (node (ref "U5") (pin "16") (pinfunction "IO10_16") (pintype "passive"))
    )
    (net (code "21") (name "/JOYSTICK1_X") (class "Default")
      (node (ref "J16") (pin "3") (pinfunction "Y-AXIS_3") (pintype "passive"))
    )
    (net (code "22") (name "/JOYSTICK1_Y") (class "Default")
      (node (ref "J16") (pin "1") (pinfunction "X-AXIS_1") (pintype "passive"))
    )
    (net (code "23") (name "/JOYSTICK2_X") (class "Default")
      (node (ref "J17") (pin "3") (pinfunction "Y-AXIS_3") (pintype "passive"))
    )
    (net (code "24") (name "/JOYSTICK2_Y") (class "Default")
      (node (ref "J17") (pin "1") (pinfunction "X-AXIS_1") (pintype "passive"))
    )
    (net (code "25") (name "/LED0") (class "Default")
      (node (ref "Q12") (pin "1") (pinfunction "G_1") (pintype "passive"))
      (node (ref "R129") (pin "1") (pinfunction "1_1") (pintype "passive"))
    )
    (net (code "26") (name "/LED1") (class "Default")
      (node (ref "Q13") (pin "1") (pinfunction "G_1") (pintype "passive"))
      (node (ref "R170") (pin "1") (pinfunction "1_1") (pintype "passive"))
    )
    (net (code "27") (name "/SCL") (class "Default")
      (node (ref "U5") (pin "26") (pinfunction "SCL_26") (pintype "passive"))
    )
    (net (code "28") (name "/SDA") (class "Default")
      (node (ref "U5") (pin "25") (pinfunction "SDA_25") (pintype "passive"))
    )
    (net (code "29") (name "/SELECT") (class "Default")
      (node (ref "R117") (pin "2") (pinfunction "2_2") (pintype "passive"))
      (node (ref "S5") (pin "1") (pinfunction "A_1") (pintype "passive"))
    )
    (net (code "30") (name "/START") (class "Default")
      (node (ref "R115") (pin "2") (pinfunction "2_2") (pintype "passive"))
      (node (ref "S1") (pin "1") (pinfunction "A_1") (pintype "passive"))
    )
    (net (code "31") (name "/TOUCH_INT_N") (class "Default")
      (node (ref "U5") (pin "22") (pinfunction "IO14_22") (pintype "passive"))
    )
    (net (code "33") (name "GND") (class "Default")
      (node (ref "C10") (pin "1") (pinfunction "1_1") (pintype "passive"))
      (node (ref "C50") (pin "1") (pinfunction "1_1") (pintype "passive"))
      (node (ref "C51") (pin "1") (pinfunction "1_1") (pintype "passive"))
      (node (ref "C52") (pin "1") (pinfunction "1_1") (pintype "passive"))
      (node (ref "C53") (pin "1") (pinfunction "1_1") (pintype "passive"))
      (node (ref "C54") (pin "1") (pinfunction "1_1") (pintype "passive"))
      (node (ref "C55") (pin "1") (pinfunction "1_1") (pintype "passive"))
      (node (ref "C56") (pin "1") (pinfunction "1_1") (pintype "passive"))
      (node (ref "C58") (pin "1") (pinfunction "1_1") (pintype "passive"))
      (node (ref "C59") (pin "1") (pinfunction "1_1") (pintype "passive"))
      (node (ref "C60") (pin "1") (pinfunction "1_1") (pintype "passive"))
      (node (ref "C61") (pin "1") (pinfunction "1_1") (pintype "passive"))
      (node (ref "C67") (pin "1") (pinfunction "1_1") (pintype "passive"))
      (node (ref "C8") (pin "1") (pinfunction "1_1") (pintype "passive"))
      (node (ref "C85") (pin "1") (pinfunction "1_1") (pintype "passive"))
      (node (ref "C87") (pin "1") (pinfunction "1_1") (pintype "passive"))
      (node (ref "C9") (pin "1") (pinfunction "1_1") (pintype "passive"))
      (node (ref "C92") (pin "1") (pinfunction "1_1") (pintype "passive"))
      (node (ref "C93") (pin "1") (pinfunction "1_1") (pintype "passive"))
      (node (ref "J16") (pin "4") (pinfunction "GND_4") (pintype "passive"))
      (node (ref "J17") (pin "4") (pinfunction "GND_4") (pintype "passive"))
      (node (ref "Q12") (pin "2") (pinfunction "S_2") (pintype "passive"))
      (node (ref "Q13") (pin "2") (pinfunction "S_2") (pintype "passive"))
      (node (ref "R129") (pin "2") (pinfunction "2_2") (pintype "passive"))
      (node (ref "R170") (pin "2") (pinfunction "2_2") (pintype "passive"))
      (node (ref "S1") (pin "3") (pinfunction "B_3") (pintype "passive"))
      (node (ref "S1") (pin "4") (pinfunction "B'_4") (pintype "passive"))
      (node (ref "S10") (pin "2") (pinfunction "2_2") (pintype "passive"))
      (node (ref "S11") (pin "2") (pinfunction "2_2") (pintype "passive"))
      (node (ref "S12") (pin "2") (pinfunction "2_2") (pintype "passive"))
      (node (ref "S13") (pin "2") (pinfunction "2_2") (pintype "passive"))
      (node (ref "S14") (pin "2") (pinfunction "2_2") (pintype "passive"))
      (node (ref "S16") (pin "1") (pinfunction "A_1") (pintype "passive"))
      (node (ref "S3") (pin "2") (pinfunction "A'_2") (pintype "passive"))
      (node (ref "S4") (pin "2") (pinfunction "A'_2") (pintype "passive"))
      (node (ref "S5") (pin "3") (pinfunction "B_3") (pintype "passive"))
      (node (ref "S5") (pin "4") (pinfunction "B'_4") (pintype "passive"))
      (node (ref "S6") (pin "1") (pinfunction "A_1") (pintype "passive"))
      (node (ref "S7") (pin "2") (pinfunction "2_2") (pintype "passive"))
      (node (ref "S8") (pin "2") (pinfunction "2_2") (pintype "passive"))
      (node (ref "S9") (pin "2") (pinfunction "2_2") (pintype "passive"))
      (node (ref "U5") (pin "1") (pinfunction "GND_1") (pintype "passive"))
      (node (ref "U5") (pin "15") (pinfunction "GND_15") (pintype "passive"))
      (node (ref "U5") (pin "21") (pinfunction "GND_21") (pintype "passive"))
      (node (ref "U5") (pin "29") (pinfunction "GND_29") (pintype "passive"))
      (node (ref "U5") (pin "7") (pinfunction "GND_7") (pintype "passive"))
    )
    (net (code "34") (name "Net-(LED3-Pad2)") (class "Default")
      (node (ref "LED3") (pin "2") (pinfunction "2_2") (pintype "passive"))
      (node (ref "R108") (pin "1") (pinfunction "1_1") (pintype "passive"))
    )
    (net (code "35") (name "Net-(LED7-Pad2)") (class "Default")
      (node (ref "LED7") (pin "2") (pinfunction "2_2") (pintype "passive"))
      (node (ref "R169") (pin "1") (pinfunction "1_1") (pintype "passive"))
    )
    (net (code "36") (name "Net-(Q12-D)") (class "Default")
      (node (ref "Q12") (pin "3") (pinfunction "D_3") (pintype "passive"))
      (node (ref "R108") (pin "2") (pinfunction "2_2") (pintype "passive"))
    )
    (net (code "37") (name "Net-(Q13-D)") (class "Default")
      (node (ref "Q13") (pin "3") (pinfunction "D_3") (pintype "passive"))
      (node (ref "R169") (pin "2") (pinfunction "2_2") (pintype "passive"))
    )
    (net (code "38") (name "Net-(R111-Pad2)") (class "Default")
      (node (ref "R111") (pin "2") (pinfunction "2_2") (pintype "passive"))
      (node (ref "S14") (pin "1") (pinfunction "1_1") (pintype "passive"))
    )
    (net (code "39") (name "Net-(R112-Pad2)") (class "Default")
      (node (ref "R112") (pin "2") (pinfunction "2_2") (pintype "passive"))
      (node (ref "S10") (pin "1") (pinfunction "1_1") (pintype "passive"))
    )
    (net (code "40") (name "Net-(R113-Pad2)") (class "Default")
      (node (ref "R113") (pin "2") (pinfunction "2_2") (pintype "passive"))
      (node (ref "S12") (pin "1") (pinfunction "1_1") (pintype "passive"))
    )
    (net (code "41") (name "Net-(R114-Pad2)") (class "Default")
      (node (ref "R114") (pin "2") (pinfunction "2_2") (pintype "passive"))
      (node (ref "S13") (pin "1") (pinfunction "1_1") (pintype "passive"))
    )
    (net (code "42") (name "Net-(R118-Pad2)") (class "Default")
      (node (ref "R118") (pin "2") (pinfunction "2_2") (pintype "passive"))
      (node (ref "S11") (pin "1") (pinfunction "1_1") (pintype "passive"))
    )
    (net (code "43") (name "Net-(R119-Pad2)") (class "Default")
      (node (ref "R119") (pin "2") (pinfunction "2_2") (pintype "passive"))
      (node (ref "S9") (pin "1") (pinfunction "1_1") (pintype "passive"))
    )
    (net (code "44") (name "Net-(R121-Pad2)") (class "Default")
      (node (ref "R121") (pin "2") (pinfunction "2_2") (pintype "passive"))
      (node (ref "S7") (pin "1") (pinfunction "1_1") (pintype "passive"))
    )
    (net (code "45") (name "Net-(R122-Pad2)") (class "Default")
      (node (ref "R122") (pin "2") (pinfunction "2_2") (pintype "passive"))
      (node (ref "S8") (pin "1") (pinfunction "1_1") (pintype "passive"))
    )
    (net (code "46") (name "Net-(S3-A)") (class "Default")
      (node (ref "R110") (pin "2") (pinfunction "2_2") (pintype "passive"))
      (node (ref "S3") (pin "1") (pinfunction "A_1") (pintype "passive"))
    )
    (net (code "47") (name "Net-(S4-A)") (class "Default")
      (node (ref "R109") (pin "2") (pinfunction "2_2") (pintype "passive"))
      (node (ref "S4") (pin "1") (pinfunction "A_1") (pintype "passive"))
    )
    (net (code "48") (name "Net-(S6-A')") (class "Default")
      (node (ref "R65") (pin "2") (pinfunction "2_2") (pintype "passive"))
      (node (ref "S6") (pin "2") (pinfunction "A'_2") (pintype "passive"))
    )
    (net (code "49") (name "Net-(S16-A')") (class "Default")
      (node (ref "R66") (pin "2") (pinfunction "2_2") (pintype "passive"))
      (node (ref "S16") (pin "2") (pinfunction "A'_2") (pintype "passive"))
    )
    (net (code "50") (name "Net-(U5-RESET_N)") (class "Default")
      (node (ref "R68") (pin "2") (pinfunction "2_2") (pintype "passive"))
      (node (ref "U5") (pin "24") (pinfunction "RESET_N_24") (pintype "passive"))
    )
    (net (code "51") (name "V1P8") (class "Default")
      (node (ref "C85") (pin "2") (pinfunction "2_2") (pintype "passive"))
      (node (ref "C87") (pin "2") (pinfunction "2_2") (pintype "passive"))
      (node (ref "J16") (pin "2") (pinfunction "VCC_2") (pintype "passive"))
      (node (ref "J17") (pin "2") (pinfunction "VCC_2") (pintype "passive"))
    )
    (net (code "52") (name "V3P3") (class "Default")
      (node (ref "C10") (pin "2") (pinfunction "2_2") (pintype "passive"))
      (node (ref "C8") (pin "2") (pinfunction "2_2") (pintype "passive"))
      (node (ref "C9") (pin "2") (pinfunction "2_2") (pintype "passive"))
      (node (ref "LED3") (pin "1") (pinfunction "1_1") (pintype "passive"))
      (node (ref "LED7") (pin "1") (pinfunction "1_1") (pintype "passive"))
      (node (ref "R68") (pin "1") (pinfunction "1_1") (pintype "passive"))
      (node (ref "R69") (pin "1") (pinfunction "1_1") (pintype "passive"))
      (node (ref "U5") (pin "12") (pinfunction "VDDM_12") (pintype "passive"))
      (node (ref "U5") (pin "18") (pinfunction "VCC2_18") (pintype "passive"))
      (node (ref "U5") (pin "4") (pinfunction "VCC1_4") (pintype "passive"))
    )
    (net (code "53") (name "unconnected-(S1-A'-Pad2)") (class "Default")
      (node (ref "S1") (pin "2") (pinfunction "A'_2") (pintype "passive+no_connect"))
    )
    (net (code "54") (name "unconnected-(S5-A'-Pad2)") (class "Default")
      (node (ref "S5") (pin "2") (pinfunction "A'_2") (pintype "passive+no_connect"))
    )
    (net (code "55") (name "unconnected-(U5-NC-Pad11)") (class "Default")
      (node (ref "U5") (pin "11") (pinfunction "NC_11") (pintype "passive+no_connect"))
    )
  )
)
